# ProPrj_DRV8701E__2025-06.net
KiCad netlist of a schematic drawn in EasyEDA Pro
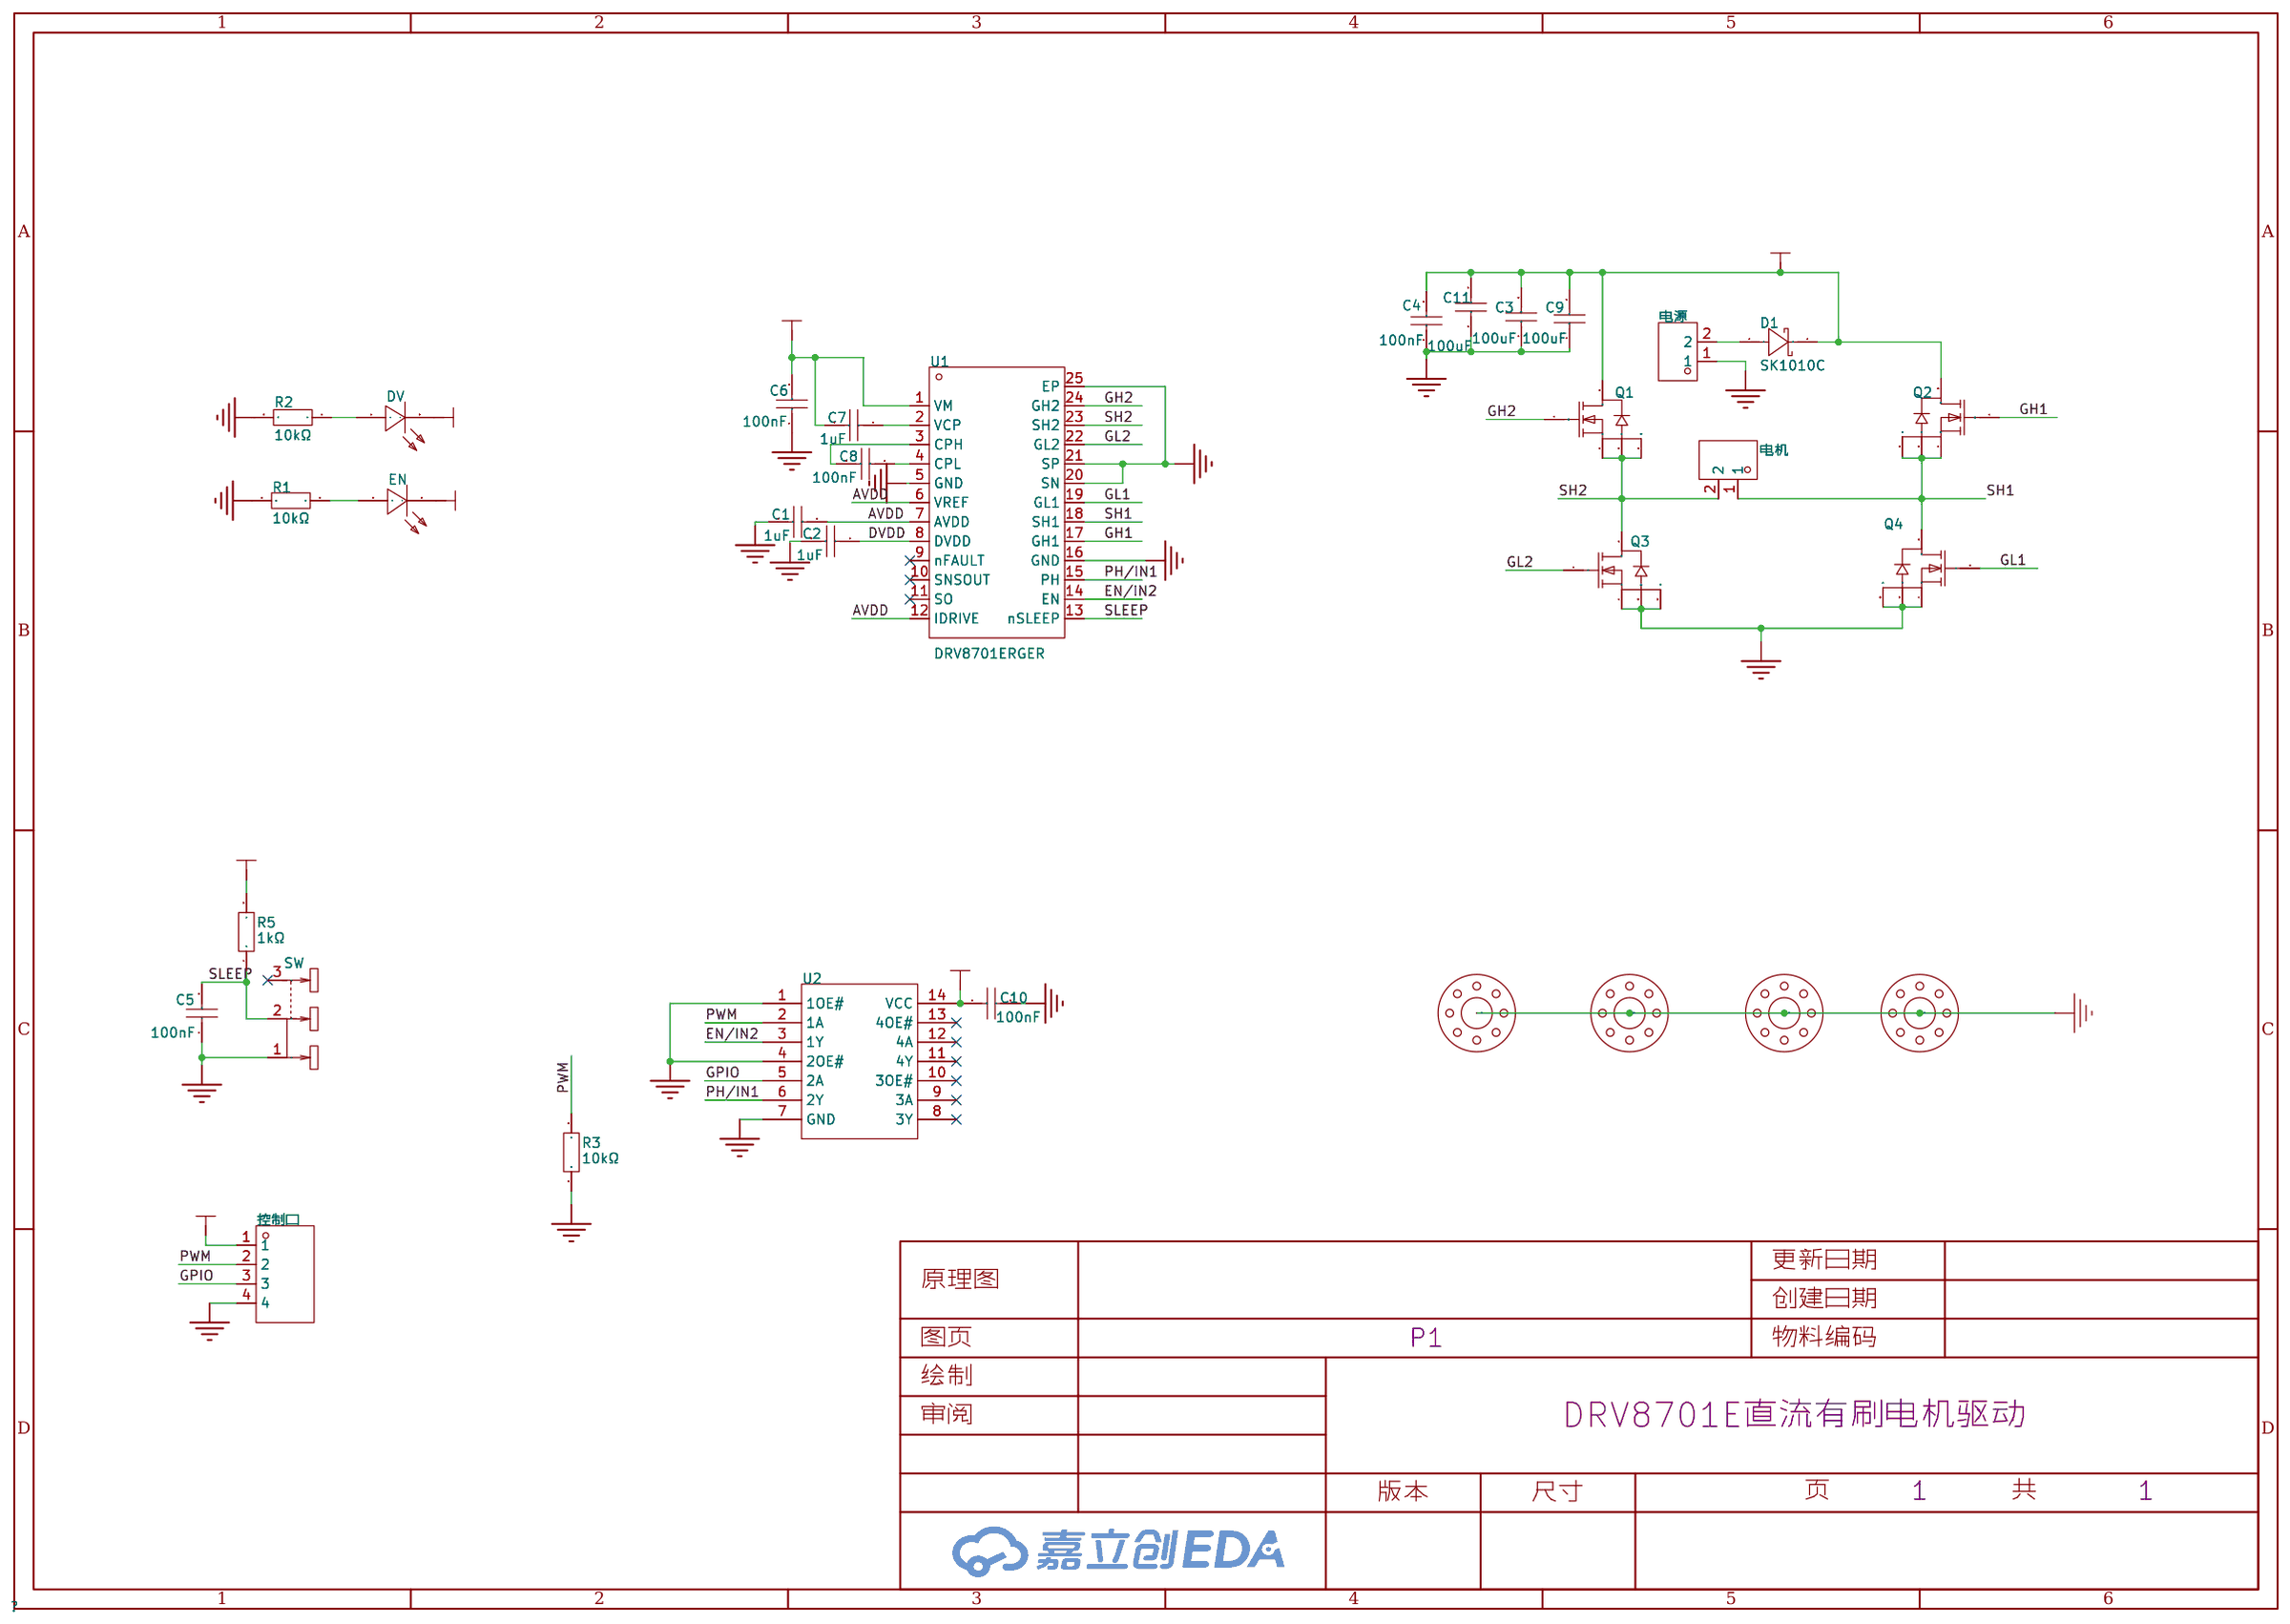
[diagram p0: schematic sheet]

(export (version "E")
  (design (tool "Eeschema 10.0.6"))
  (components
    (comp (ref "C1")
      (value "1uF")
      (footprint "easyedapro:C0805")
      (description "容值:1uF;精度:±10%;额定电压:50V;材质(温度系数):X7R;")
      (fields
        (field (name "Manufacturer Part") "CL21B105KBFNNNE")
        (field (name "Manufacturer") "SAMSUNG(三星)")
      )
      (libsource (lib "easyedapro") (part "CL21B105KBFNNNE"))
    )
    (comp (ref "C2")
      (value "1uF")
      (footprint "easyedapro:C0805")
      (description "容值:1uF;精度:±10%;额定电压:50V;材质(温度系数):X7R;")
      (fields
        (field (name "Manufacturer Part") "CL21B105KBFNNNE")
        (field (name "Manufacturer") "SAMSUNG(三星)")
      )
      (libsource (lib "easyedapro") (part "CL21B105KBFNNNE"))
    )
    (comp (ref "C3")
      (value "100uF")
      (footprint "easyedapro:C0805")
      (description "容值:100uF;精度:±20%;额定电压:6.3V;材质(温度系数):X5R;")
      (fields
        (field (name "Manufacturer Part") "GRM21BR60J107ME15L")
        (field (name "Manufacturer") "muRata(村田)")
      )
      (libsource (lib "easyedapro") (part "GRM21BR60J107ME15L"))
    )
    (comp (ref "C4")
      (value "100nF")
      (footprint "easyedapro:C0805")
      (description "容值:100nF;精度:±10%;额定电压:50V;材质(温度系数):X7R;")
      (fields
        (field (name "Manufacturer Part") "CC0805KRX7R9BB104")
        (field (name "Manufacturer") "YAGEO(国巨)")
      )
      (libsource (lib "easyedapro") (part "CC0805KRX7R9BB104"))
    )
    (comp (ref "C5")
      (value "100nF")
      (footprint "easyedapro:C0805")
      (description "容值:100nF;精度:±10%;额定电压:50V;材质(温度系数):X7R;")
      (fields
        (field (name "Manufacturer Part") "CC0805KRX7R9BB104")
        (field (name "Manufacturer") "YAGEO(国巨)")
      )
      (libsource (lib "easyedapro") (part "CC0805KRX7R9BB104"))
    )
    (comp (ref "C6")
      (value "100nF")
      (footprint "easyedapro:C0805")
      (description "容值:100nF;精度:±10%;额定电压:50V;材质(温度系数):X7R;")
      (fields
        (field (name "Manufacturer Part") "CC0805KRX7R9BB104")
        (field (name "Manufacturer") "YAGEO(国巨)")
      )
      (libsource (lib "easyedapro") (part "CC0805KRX7R9BB104"))
    )
    (comp (ref "C7")
      (value "1uF")
      (footprint "easyedapro:C0805")
      (description "容值:1uF;精度:±10%;额定电压:50V;材质(温度系数):X7R;")
      (fields
        (field (name "Manufacturer Part") "CL21B105KBFNNNE")
        (field (name "Manufacturer") "SAMSUNG(三星)")
      )
      (libsource (lib "easyedapro") (part "CL21B105KBFNNNE"))
    )
    (comp (ref "C8")
      (value "100nF")
      (footprint "easyedapro:C0805")
      (description "容值:100nF;精度:±10%;额定电压:50V;材质(温度系数):X7R;")
      (fields
        (field (name "Manufacturer Part") "CC0805KRX7R9BB104")
        (field (name "Manufacturer") "YAGEO(国巨)")
      )
      (libsource (lib "easyedapro") (part "CC0805KRX7R9BB104"))
    )
    (comp (ref "C9")
      (value "100uF")
      (footprint "easyedapro:C0805")
      (description "容值:100uF;精度:±20%;额定电压:6.3V;材质(温度系数):X5R;")
      (fields
        (field (name "Manufacturer Part") "GRM21BR60J107ME15L")
        (field (name "Manufacturer") "muRata(村田)")
      )
      (libsource (lib "easyedapro") (part "GRM21BR60J107ME15L"))
    )
    (comp (ref "C10")
      (value "100nF")
      (footprint "easyedapro:C0805")
      (description "容值:100nF;精度:±10%;额定电压:50V;材质(温度系数):X7R;")
      (fields
        (field (name "Manufacturer Part") "CC0805KRX7R9BB104")
        (field (name "Manufacturer") "YAGEO(国巨)")
      )
      (libsource (lib "easyedapro") (part "CC0805KRX7R9BB104"))
    )
    (comp (ref "C11")
      (value "100uF")
      (footprint "easyedapro:C0805")
      (description "容值:100uF;精度:±20%;额定电压:6.3V;材质(温度系数):X5R;")
      (fields
        (field (name "Manufacturer Part") "GRM21BR60J107ME15L")
        (field (name "Manufacturer") "muRata(村田)")
      )
      (libsource (lib "easyedapro") (part "GRM21BR60J107ME15L"))
    )
    (comp (ref "D1")
      (value "SK1010C")
      (footprint "easyedapro:SMC_L6.9-W5.9-LS7.9-RD")
      (description "二极管配置:独立式;正向压降(Vf):850mV@10A;直流反向耐压(Vr):100V;平均整流电流(Io):10A;")
      (fields (field (name "Manufacturer") "宏迦橙"))
      (libsource (lib "easyedapro") (part "SK1010C_C18199193"))
    )
    (comp (ref "DV")
      (value "NCD0805R1")
      (footprint "easyedapro:LED0805-R-RD")
      (fields (field (name "Manufacturer") "国星光电"))
      (libsource (lib "easyedapro") (part "FC-2012HRK-620D"))
    )
    (comp (ref "EN")
      (value "NCD0805R1")
      (footprint "easyedapro:LED0805-R-RD")
      (fields (field (name "Manufacturer") "国星光电"))
      (libsource (lib "easyedapro") (part "FC-2012HRK-620D"))
    )
    (comp (ref "I1")
      (value "POSITION")
      (footprint "easyedapro:定位孔")
      (description "定位孔")
      (libsource (lib "easyedapro") (part "POSITION"))
    )
    (comp (ref "I2")
      (value "POSITION")
      (footprint "easyedapro:定位孔")
      (description "定位孔")
      (libsource (lib "easyedapro") (part "POSITION"))
    )
    (comp (ref "I3")
      (value "POSITION")
      (footprint "easyedapro:定位孔")
      (description "定位孔")
      (libsource (lib "easyedapro") (part "POSITION"))
    )
    (comp (ref "I4")
      (value "POSITION")
      (footprint "easyedapro:定位孔")
      (description "定位孔")
      (libsource (lib "easyedapro") (part "POSITION"))
    )
    (comp (ref "Q1")
      (value "TPH1R403NL")
      (footprint "easyedapro:TDSON-8_L5.9-W5.2-P1.27-BL")
      (fields (field (name "Manufacturer") "TECH PUBLIC(台舟)"))
      (libsource (lib "easyedapro") (part "TPH1R403NL_C19268167"))
    )
    (comp (ref "Q2")
      (value "TPH1R403NL")
      (footprint "easyedapro:TDSON-8_L5.9-W5.2-P1.27-BL")
      (fields (field (name "Manufacturer") "TECH PUBLIC(台舟)"))
      (libsource (lib "easyedapro") (part "TPH1R403NL_C19268167"))
    )
    (comp (ref "Q3")
      (value "TPH1R403NL")
      (footprint "easyedapro:TDSON-8_L5.9-W5.2-P1.27-BL")
      (fields (field (name "Manufacturer") "TECH PUBLIC(台舟)"))
      (libsource (lib "easyedapro") (part "TPH1R403NL_C19268167"))
    )
    (comp (ref "Q4")
      (value "TPH1R403NL")
      (footprint "easyedapro:TDSON-8_L5.9-W5.2-P1.27-BL")
      (fields (field (name "Manufacturer") "TECH PUBLIC(台舟)"))
      (libsource (lib "easyedapro") (part "TPH1R403NL_C19268167"))
    )
    (comp (ref "R1")
      (value "10kΩ")
      (footprint "easyedapro:R0805")
      (description "电阻类型:厚膜电阻;阻值:10kΩ;精度:±1%;功率:125mW;最大工作电压:150V;温度系数:±100ppm/°C;")
      (fields
        (field (name "Manufacturer Part") "0805W8F1002T5E")
        (field (name "Manufacturer") "UNI-ROYAL(厚声)")
      )
      (libsource (lib "easyedapro") (part "0805W8F1002T5E"))
    )
    (comp (ref "R2")
      (value "10kΩ")
      (footprint "easyedapro:R0805")
      (description "电阻类型:厚膜电阻;阻值:10kΩ;精度:±1%;功率:125mW;最大工作电压:150V;温度系数:±100ppm/°C;")
      (fields
        (field (name "Manufacturer Part") "0805W8F1002T5E")
        (field (name "Manufacturer") "UNI-ROYAL(厚声)")
      )
      (libsource (lib "easyedapro") (part "0805W8F1002T5E"))
    )
    (comp (ref "R3")
      (value "10kΩ")
      (footprint "easyedapro:R0805")
      (description "电阻类型:厚膜电阻;阻值:10kΩ;精度:±1%;功率:125mW;最大工作电压:150V;温度系数:±100ppm/°C;")
      (fields
        (field (name "Manufacturer Part") "0805W8F1002T5E")
        (field (name "Manufacturer") "UNI-ROYAL(厚声)")
      )
      (libsource (lib "easyedapro") (part "0805W8F1002T5E"))
    )
    (comp (ref "R5")
      (value "1kΩ")
      (footprint "easyedapro:R0805")
      (description "电阻类型:厚膜电阻;阻值:1kΩ;精度:±1%;功率:125mW;最大工作电压:150V;温度系数:±100ppm/°C;")
      (fields
        (field (name "Manufacturer Part") "0805W8F1001T5E")
        (field (name "Manufacturer") "UNI-ROYAL(厚声)")
      )
      (libsource (lib "easyedapro") (part "0805W8F1001T5E"))
    )
    (comp (ref "SW")
      (value "SS-12D10L5")
      (footprint "easyedapro:SW-TH_SS-12D10L5")
      (description "电路结构:单刀双掷;安装方式:直插;开关颜色:黑色;额定电流(DC):3A;额定电压(DC):125V;额定电流(AC):3A;额定电压(AC):125V;机械寿命:1万次;")
      (fields (field (name "Manufacturer") "XKB Connectivity(中国星坤)"))
      (libsource (lib "easyedapro") (part "SS-12D10L5"))
    )
    (comp (ref "U1")
      (value "DRV8701ERGER")
      (footprint "easyedapro:VQFN-24_L4.0-W4.0-P0.50-BL-EP2.5")
      (description "驱动电机类型:有刷直流电机;电源电压:5.9V~45V;输出电流:-;接口:并行;")
      (fields (field (name "Manufacturer") "TI(德州仪器)"))
      (libsource (lib "easyedapro") (part "DRV8701ERGER"))
    )
    (comp (ref "U2")
      (value "74HC125PW,118")
      (footprint "easyedapro:TSSOP-14_L5.0-W4.4-P0.65-LS6.4-BL")
      (description "输入类型:-;电源电压:2V~6V;元件数:4;每个元件位数:1;灌电流(IOL):7.8mA;拉电流(IOH):7.8mA;")
      (fields (field (name "Manufacturer") "Nexperia(安世)"))
      (libsource (lib "easyedapro") (part "74HC125PW,118"))
    )
    (comp (ref "控制口")
      (value "S4B-PH-K-S(LF)(SN)")
      (footprint "easyedapro:CONN-TH_4P-P2.00_S4B-PH-K-S-LF-SN")
      (description "插针结构:1x4P;间距:2mm;安装方式:弯插;参考系列:PH;总PIN数:4P;排数:1;每排PIN数:4;行距:-;触头材质:黄铜;")
      (fields (field (name "Manufacturer") "JST"))
      (libsource (lib "easyedapro") (part "S4B-PH-K-S-(LF)(SN)"))
    )
    (comp (ref "电机")
      (value "DB302-5.0-2P-GN-S")
      (footprint "easyedapro:CONN-TH_DB302-5.0-2P")
      (fields (field (name "Manufacturer") "DORABO(地博电气)"))
      (libsource (lib "easyedapro") (part "DB302-5.0-2P-GN-S"))
    )
    (comp (ref "电源")
      (value "DB302-5.0-2P-GN-S")
      (footprint "easyedapro:CONN-TH_DB302-5.0-2P")
      (fields (field (name "Manufacturer") "DORABO(地博电气)"))
      (libsource (lib "easyedapro") (part "DB302-5.0-2P-GN-S"))
    )
  )
  (nets
    (net (code "1") (name "/AVDD") (class "Default")
      (node (ref "C1") (pin "2") (pinfunction "2_2") (pintype "input"))
      (node (ref "U1") (pin "12") (pinfunction "IDRIVE_12") (pintype "input"))
      (node (ref "U1") (pin "6") (pinfunction "VREF_6") (pintype "input"))
      (node (ref "U1") (pin "7") (pinfunction "AVDD_7") (pintype "input"))
    )
    (net (code "2") (name "/DVDD") (class "Default")
      (node (ref "C2") (pin "1") (pinfunction "1_1") (pintype "input"))
      (node (ref "U1") (pin "8") (pinfunction "DVDD_8") (pintype "input"))
    )
    (net (code "3") (name "/EN{slash}IN2") (class "Default")
      (node (ref "U1") (pin "14") (pinfunction "EN_14") (pintype "input"))
      (node (ref "U2") (pin "3") (pinfunction "1Y_3") (pintype "input"))
    )
    (net (code "4") (name "/GH1") (class "Default")
      (node (ref "Q2") (pin "4") (pinfunction "G_4") (pintype "unspecified"))
      (node (ref "U1") (pin "17") (pinfunction "GH1_17") (pintype "input"))
    )
    (net (code "5") (name "/GH2") (class "Default")
      (node (ref "Q1") (pin "4") (pinfunction "G_4") (pintype "unspecified"))
      (node (ref "U1") (pin "24") (pinfunction "GH2_24") (pintype "input"))
    )
    (net (code "6") (name "/GL1") (class "Default")
      (node (ref "Q4") (pin "4") (pinfunction "G_4") (pintype "unspecified"))
      (node (ref "U1") (pin "19") (pinfunction "GL1_19") (pintype "input"))
    )
    (net (code "7") (name "/GL2") (class "Default")
      (node (ref "Q3") (pin "4") (pinfunction "G_4") (pintype "unspecified"))
      (node (ref "U1") (pin "22") (pinfunction "GL2_22") (pintype "input"))
    )
    (net (code "8") (name "/GPIO") (class "Default")
      (node (ref "U2") (pin "5") (pinfunction "2A_5") (pintype "input"))
      (node (ref "控制口") (pin "3") (pinfunction "3_3") (pintype "unspecified"))
    )
    (net (code "9") (name "/PH{slash}IN1") (class "Default")
      (node (ref "U1") (pin "15") (pinfunction "PH_15") (pintype "input"))
      (node (ref "U2") (pin "6") (pinfunction "2Y_6") (pintype "input"))
    )
    (net (code "10") (name "/PWM") (class "Default")
      (node (ref "R3") (pin "1") (pinfunction "1_1") (pintype "input"))
      (node (ref "U2") (pin "2") (pinfunction "1A_2") (pintype "input"))
      (node (ref "控制口") (pin "2") (pinfunction "2_2") (pintype "unspecified"))
    )
    (net (code "11") (name "/SH1") (class "Default")
      (node (ref "Q2") (pin "1") (pinfunction "S_1") (pintype "unspecified"))
      (node (ref "Q2") (pin "2") (pinfunction "S_2") (pintype "unspecified"))
      (node (ref "Q2") (pin "3") (pinfunction "S_3") (pintype "unspecified"))
      (node (ref "Q4") (pin "5") (pinfunction "D_5") (pintype "unspecified"))
      (node (ref "U1") (pin "18") (pinfunction "SH1_18") (pintype "input"))
      (node (ref "电机") (pin "1") (pinfunction "1_1") (pintype "unspecified"))
    )
    (net (code "12") (name "/SH2") (class "Default")
      (node (ref "Q1") (pin "1") (pinfunction "S_1") (pintype "unspecified"))
      (node (ref "Q1") (pin "2") (pinfunction "S_2") (pintype "unspecified"))
      (node (ref "Q1") (pin "3") (pinfunction "S_3") (pintype "unspecified"))
      (node (ref "Q3") (pin "5") (pinfunction "D_5") (pintype "unspecified"))
      (node (ref "U1") (pin "23") (pinfunction "SH2_23") (pintype "input"))
      (node (ref "电机") (pin "2") (pinfunction "2_2") (pintype "unspecified"))
    )
    (net (code "13") (name "3V3") (class "Default")
      (node (ref "C10") (pin "2") (pinfunction "2_2") (pintype "input"))
      (node (ref "R5") (pin "2") (pinfunction "2_2") (pintype "input"))
      (node (ref "U2") (pin "14") (pinfunction "VCC_14") (pintype "input"))
      (node (ref "控制口") (pin "1") (pinfunction "1_1") (pintype "unspecified"))
    )
    (net (code "14") (name "GND") (class "Default")
      (node (ref "C1") (pin "1") (pinfunction "1_1") (pintype "input"))
      (node (ref "C10") (pin "1") (pinfunction "1_1") (pintype "input"))
      (node (ref "C11") (pin "1") (pinfunction "1_1") (pintype "input"))
      (node (ref "C2") (pin "2") (pinfunction "2_2") (pintype "input"))
      (node (ref "C3") (pin "1") (pinfunction "1_1") (pintype "input"))
      (node (ref "C4") (pin "1") (pinfunction "1_1") (pintype "input"))
      (node (ref "C5") (pin "1") (pinfunction "1_1") (pintype "input"))
      (node (ref "C6") (pin "1") (pinfunction "1_1") (pintype "input"))
      (node (ref "C9") (pin "1") (pinfunction "1_1") (pintype "input"))
      (node (ref "I1") (pin "0") (pinfunction "0_0") (pintype "unspecified"))
      (node (ref "I2") (pin "0") (pinfunction "0_0") (pintype "unspecified"))
      (node (ref "I3") (pin "0") (pinfunction "0_0") (pintype "unspecified"))
      (node (ref "I4") (pin "0") (pinfunction "0_0") (pintype "unspecified"))
      (node (ref "Q3") (pin "1") (pinfunction "S_1") (pintype "unspecified"))
      (node (ref "Q3") (pin "2") (pinfunction "S_2") (pintype "unspecified"))
      (node (ref "Q3") (pin "3") (pinfunction "S_3") (pintype "unspecified"))
      (node (ref "Q4") (pin "1") (pinfunction "S_1") (pintype "unspecified"))
      (node (ref "Q4") (pin "2") (pinfunction "S_2") (pintype "unspecified"))
      (node (ref "Q4") (pin "3") (pinfunction "S_3") (pintype "unspecified"))
      (node (ref "R1") (pin "2") (pinfunction "2_2") (pintype "input"))
      (node (ref "R2") (pin "2") (pinfunction "2_2") (pintype "input"))
      (node (ref "R3") (pin "2") (pinfunction "2_2") (pintype "input"))
      (node (ref "SW") (pin "1") (pinfunction "1_1") (pintype "unspecified"))
      (node (ref "U1") (pin "16") (pinfunction "GND_16") (pintype "input"))
      (node (ref "U1") (pin "20") (pinfunction "SN_20") (pintype "input"))
      (node (ref "U1") (pin "21") (pinfunction "SP_21") (pintype "input"))
      (node (ref "U1") (pin "25") (pinfunction "EP_25") (pintype "input"))
      (node (ref "U1") (pin "5") (pinfunction "GND_5") (pintype "input"))
      (node (ref "U2") (pin "1") (pinfunction "1OE#_1") (pintype "input"))
      (node (ref "U2") (pin "4") (pinfunction "2OE#_4") (pintype "input"))
      (node (ref "U2") (pin "7") (pinfunction "GND_7") (pintype "input"))
      (node (ref "控制口") (pin "4") (pinfunction "4_4") (pintype "unspecified"))
      (node (ref "电源") (pin "1") (pinfunction "1_1") (pintype "unspecified"))
    )
    (net (code "15") (name "Net-(D1-A)") (class "Default")
      (node (ref "D1") (pin "2") (pinfunction "A_2") (pintype "unspecified"))
      (node (ref "电源") (pin "2") (pinfunction "2_2") (pintype "unspecified"))
    )
    (net (code "16") (name "Net-(DV-+)") (class "Default")
      (node (ref "DV") (pin "1") (pinfunction "+_1") (pintype "unspecified"))
      (node (ref "R2") (pin "1") (pinfunction "1_1") (pintype "input"))
    )
    (net (code "17") (name "Net-(EN-+)") (class "Default")
      (node (ref "EN") (pin "1") (pinfunction "+_1") (pintype "unspecified"))
      (node (ref "R1") (pin "1") (pinfunction "1_1") (pintype "input"))
    )
    (net (code "18") (name "Net-(U1-CPH)") (class "Default")
      (node (ref "C8") (pin "2") (pinfunction "2_2") (pintype "input"))
      (node (ref "U1") (pin "3") (pinfunction "CPH_3") (pintype "input"))
    )
    (net (code "19") (name "Net-(U1-CPL)") (class "Default")
      (node (ref "C8") (pin "1") (pinfunction "1_1") (pintype "input"))
      (node (ref "U1") (pin "4") (pinfunction "CPL_4") (pintype "input"))
    )
    (net (code "20") (name "Net-(U1-VCP)") (class "Default")
      (node (ref "C7") (pin "1") (pinfunction "1_1") (pintype "input"))
      (node (ref "U1") (pin "2") (pinfunction "VCP_2") (pintype "input"))
    )
    (net (code "21") (name "SLEEP") (class "Default")
      (node (ref "C5") (pin "2") (pinfunction "2_2") (pintype "input"))
      (node (ref "EN") (pin "2") (pinfunction "-_2") (pintype "unspecified"))
      (node (ref "R5") (pin "1") (pinfunction "1_1") (pintype "input"))
      (node (ref "SW") (pin "2") (pinfunction "2_2") (pintype "unspecified"))
      (node (ref "U1") (pin "13") (pinfunction "nSLEEP_13") (pintype "input"))
    )
    (net (code "22") (name "VM") (class "Default")
      (node (ref "C11") (pin "2") (pinfunction "2_2") (pintype "input"))
      (node (ref "C3") (pin "2") (pinfunction "2_2") (pintype "input"))
      (node (ref "C4") (pin "2") (pinfunction "2_2") (pintype "input"))
      (node (ref "C6") (pin "2") (pinfunction "2_2") (pintype "input"))
      (node (ref "C7") (pin "2") (pinfunction "2_2") (pintype "input"))
      (node (ref "C9") (pin "2") (pinfunction "2_2") (pintype "input"))
      (node (ref "D1") (pin "1") (pinfunction "K_1") (pintype "unspecified"))
      (node (ref "DV") (pin "2") (pinfunction "-_2") (pintype "unspecified"))
      (node (ref "Q1") (pin "5") (pinfunction "D_5") (pintype "unspecified"))
      (node (ref "Q2") (pin "5") (pinfunction "D_5") (pintype "unspecified"))
      (node (ref "U1") (pin "1") (pinfunction "VM_1") (pintype "input"))
    )
    (net (code "23") (name "unconnected-(SW-Pad3)") (class "Default")
      (node (ref "SW") (pin "3") (pinfunction "3_3") (pintype "unspecified+no_connect"))
    )
    (net (code "24") (name "unconnected-(U1-SNSOUT-Pad10)") (class "Default")
      (node (ref "U1") (pin "10") (pinfunction "SNSOUT_10") (pintype "input+no_connect"))
    )
    (net (code "25") (name "unconnected-(U1-SO-Pad11)") (class "Default")
      (node (ref "U1") (pin "11") (pinfunction "SO_11") (pintype "input+no_connect"))
    )
    (net (code "26") (name "unconnected-(U1-nFAULT-Pad9)") (class "Default")
      (node (ref "U1") (pin "9") (pinfunction "nFAULT_9") (pintype "input+no_connect"))
    )
    (net (code "27") (name "unconnected-(U2-3A-Pad9)") (class "Default")
      (node (ref "U2") (pin "9") (pinfunction "3A_9") (pintype "input+no_connect"))
    )
    (net (code "28") (name "unconnected-(U2-3OE#-Pad10)") (class "Default")
      (node (ref "U2") (pin "10") (pinfunction "3OE#_10") (pintype "input+no_connect"))
    )
    (net (code "29") (name "unconnected-(U2-3Y-Pad8)") (class "Default")
      (node (ref "U2") (pin "8") (pinfunction "3Y_8") (pintype "input+no_connect"))
    )
    (net (code "30") (name "unconnected-(U2-4A-Pad12)") (class "Default")
      (node (ref "U2") (pin "12") (pinfunction "4A_12") (pintype "input+no_connect"))
    )
    (net (code "31") (name "unconnected-(U2-4OE#-Pad13)") (class "Default")
      (node (ref "U2") (pin "13") (pinfunction "4OE#_13") (pintype "input+no_connect"))
    )
    (net (code "32") (name "unconnected-(U2-4Y-Pad11)") (class "Default")
      (node (ref "U2") (pin "11") (pinfunction "4Y_11") (pintype "input+no_connect"))
    )
  )
)
